# Sheet2.net
KiCad netlist of a schematic drawn in Altium Designer
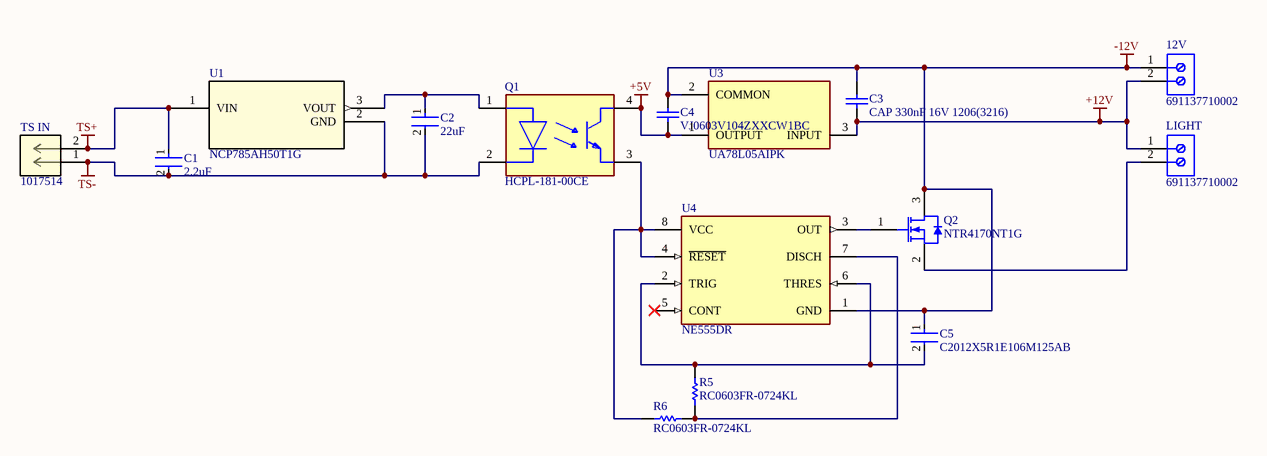
[diagram p0: Sheet2.SchDoc]

(export (version "E")
  (design (tool "Eeschema 10.0.6"))
  (components
    (comp (ref "12V")
      (value "691137710002")
      (footprint "691137710002")
      (libsource (lib "Altium Content Vault") (part "TBL - 1R - 02P - Screw"))
    )
    (comp (ref "C1")
      (value "2.2uF")
      (footprint "FP-C5750-250-0_4-IPC_C")
      (description "Multilayer Ceramic Capacitors 2.2uF ±20% 450V X6S SMD 2220")
      (fields (field (name "TOLERANCE") "20%"))
      (libsource (lib "Altium Content Vault") (part "b4654b650e69147ec39a6b967a45e02"))
    )
    (comp (ref "C2")
      (value "22uF")
      (footprint "FP-GRM21B-0_15-MFG")
      (description "Chip Multilayer Ceramic Capacitors for General Purpose, 0805, 22uF, X5R, 15%, 20%, 6.3V")
      (fields (field (name "VOLTAGE") "6.3V") (field (name "TOLERANCE") "20%"))
      (libsource (lib "Altium Content Vault") (part "b4654b650e69147ec39a6b967a45e02"))
    )
    (comp (ref "C3")
      (value "CAP 330nF 16V 1206(3216)")
      (footprint "CAPC1206(3216)110_M")
      (description "CAP 330nF 16V ±10% 1206 (3216 Metric) Thickness 1.05mm SMD")
      (fields (field (name "TOLERANCE") "Â±10%"))
      (libsource (lib "Altium Content Vault") (part "CAP"))
    )
    (comp (ref "C4")
      (value "VJ0603V104ZXXCW1BC")
      (footprint "CAPC1608X95X40ML15T15")
      (fields (field (name "MANUFACTURER") "Vitramon"))
      (libsource (lib "Altium Content Vault") (part "CAP"))
    )
    (comp (ref "C5")
      (value "C2012X5R1E106M125AB")
      (footprint "FP-C2012-125-0_2-MFG")
      (description "Multilayer Ceramic Capacitors 10μF ±20% 25V X5R SMD 0805")
      (fields (field (name "TOLERANCE") "20%"))
      (libsource (lib "Altium Content Vault") (part "b4654b650e69147ec39a6b967a45e02"))
    )
    (comp (ref "LIGHT")
      (value "691137710002")
      (footprint "691137710002")
      (libsource (lib "Altium Content Vault") (part "TBL - 1R - 02P - Screw"))
    )
    (comp (ref "Q1")
      (value "HCPL-181-00CE")
      (footprint "FP-SO-4-MFG")
      (description "OPTOISO 3.75KV TRANS 4MINIFLAT")
      (fields
        (field (name "OCTOPART") "https://octopart.com/hcpl-181-00ce-broadcom-71128032")
        (field (name "MANUFACTURER") "Broadcom")
      )
      (libsource (lib "Altium Content Vault") (part "474a932ecb3e108566a9d84ede16557"))
    )
    (comp (ref "Q2")
      (value "NTR4170NT1G")
      (footprint "ONSC-SOT-23-3-318-08_V")
      (description "Power MOSFET, 30 V, 3.1 A, Single N-Channe, 3-Pin SOT-23, Pb-Free, Tape and Reel")
      (fields (field (name "MANUFACTURER") "On Semiconductor"))
      (libsource (lib "Altium Content Vault") (part "ONSC-NMOS-G1S2D3-3"))
    )
    (comp (ref "R5")
      (value "RC0603FR-0724KL")
      (footprint "RESC1608X55X25NL10T15")
      (fields (field (name "MANUFACTURER") "Yageo"))
      (libsource (lib "Altium Content Vault") (part "RES"))
    )
    (comp (ref "R6")
      (value "RC0603FR-0724KL")
      (footprint "RESC1608X55X25NL10T15")
      (fields (field (name "MANUFACTURER") "Yageo"))
      (libsource (lib "Altium Content Vault") (part "RES"))
    )
    (comp (ref "TS IN")
      (value "1017514")
      (footprint "CONN_1017514")
      (description "Barrier Strip Terminal Block")
      (libsource (lib "UWindsor Formula Electric") (part "1017514-Symbol-1"))
    )
    (comp (ref "U1")
      (value "NCP785AH50T1G")
      (footprint "SOT-89-3_2P7X4P7_ONS")
      (description "No Description Available")
      (libsource (lib "NCP785AH50T1G") (part "NCP785AH50T1G"))
    )
    (comp (ref "U3")
      (value "UA78L05AIPK")
      (footprint "FP-PK0003A-MFG")
      (description "IC REG LINEAR 5V 100MA SOT89-3")
      (fields
        (field (name "MANUFACTURER") "Texas Instruments")
        (field (name "OCTOPART") "https://octopart.com/ua78l05aipk-texas+instruments-525592")
      )
      (libsource (lib "Altium Content Vault") (part "58e5423477dba73b0af001d1dc47a63"))
    )
    (comp (ref "U4")
      (value "NE555DR")
      (footprint "FP-D0008A-IPC_A")
      (description "IC OSC SGL TIMER 100KHZ 8-SOIC")
      (libsource (lib "Altium Content Vault") (part "a29bba90211dec1890110b94dad7d53"))
    )
  )
  (nets
    (net (code "1") (name "+5V") (class "Default")
      (node (ref "C4") (pin "1") (pinfunction "1_1") (pintype "passive"))
      (node (ref "Q1") (pin "4") (pinfunction "C_4") (pintype "passive"))
      (node (ref "U3") (pin "1") (pinfunction "OUTPUT_1") (pintype "power_in"))
    )
    (net (code "2") (name "+12V") (class "Default")
      (node (ref "12V") (pin "2") (pinfunction "2_2") (pintype "passive"))
      (node (ref "C3") (pin "1") (pinfunction "1_1") (pintype "passive"))
      (node (ref "LIGHT") (pin "1") (pinfunction "1_1") (pintype "passive"))
      (node (ref "U3") (pin "3") (pinfunction "INPUT_3") (pintype "power_in"))
    )
    (net (code "3") (name "-12V") (class "Default")
      (node (ref "12V") (pin "1") (pinfunction "1_1") (pintype "passive"))
      (node (ref "C3") (pin "2") (pinfunction "2_2") (pintype "passive"))
      (node (ref "C4") (pin "2") (pinfunction "2_2") (pintype "passive"))
      (node (ref "C5") (pin "1") (pinfunction "1_1") (pintype "passive"))
      (node (ref "Q2") (pin "3") (pinfunction "D_3") (pintype "passive"))
      (node (ref "U3") (pin "2") (pinfunction "COMMON_2") (pintype "passive"))
      (node (ref "U4") (pin "1") (pinfunction "GND_1") (pintype "power_in"))
    )
    (net (code "4") (name "Net-(Q1-A)") (class "Default")
      (node (ref "C2") (pin "1") (pinfunction "1_1") (pintype "passive"))
      (node (ref "Q1") (pin "1") (pinfunction "A_1") (pintype "passive"))
      (node (ref "U1") (pin "3") (pinfunction "VOUT_3") (pintype "output"))
    )
    (net (code "5") (name "Net-(Q1-E)") (class "Default")
      (node (ref "Q1") (pin "3") (pinfunction "E_3") (pintype "passive"))
      (node (ref "R6") (pin "1") (pinfunction "1_1") (pintype "passive"))
      (node (ref "U4") (pin "4") (pinfunction "~{RESET}_4") (pintype "input"))
      (node (ref "U4") (pin "8") (pinfunction "VCC_8") (pintype "power_in"))
    )
    (net (code "6") (name "Net-(Q2-G)") (class "Default")
      (node (ref "Q2") (pin "1") (pinfunction "G_1") (pintype "passive"))
      (node (ref "U4") (pin "3") (pinfunction "OUT_3") (pintype "output"))
    )
    (net (code "7") (name "Net-(Q2-S)") (class "Default")
      (node (ref "LIGHT") (pin "2") (pinfunction "2_2") (pintype "passive"))
      (node (ref "Q2") (pin "2") (pinfunction "S_2") (pintype "passive"))
    )
    (net (code "8") (name "Net-(U4-DISCH)") (class "Default")
      (node (ref "R5") (pin "1") (pinfunction "1_1") (pintype "passive"))
      (node (ref "R6") (pin "2") (pinfunction "2_2") (pintype "passive"))
      (node (ref "U4") (pin "7") (pinfunction "DISCH_7") (pintype "open_collector"))
    )
    (net (code "9") (name "Net-(U4-THRES)") (class "Default")
      (node (ref "C5") (pin "2") (pinfunction "2_2") (pintype "passive"))
      (node (ref "R5") (pin "2") (pinfunction "2_2") (pintype "passive"))
      (node (ref "U4") (pin "2") (pinfunction "TRIG_2") (pintype "input"))
      (node (ref "U4") (pin "6") (pinfunction "THRES_6") (pintype "input"))
    )
    (net (code "10") (name "TS+") (class "Default")
      (node (ref "C1") (pin "1") (pinfunction "1_1") (pintype "passive"))
      (node (ref "TS IN") (pin "2") (pinfunction "2_2") (pintype "passive"))
      (node (ref "U1") (pin "1") (pinfunction "VIN_1") (pintype "passive"))
    )
    (net (code "11") (name "TS-") (class "Default")
      (node (ref "C1") (pin "2") (pinfunction "2_2") (pintype "passive"))
      (node (ref "C2") (pin "2") (pinfunction "2_2") (pintype "passive"))
      (node (ref "Q1") (pin "2") (pinfunction "C_2") (pintype "passive"))
      (node (ref "TS IN") (pin "1") (pinfunction "1_1") (pintype "passive"))
      (node (ref "U1") (pin "2") (pinfunction "GND_2") (pintype "power_in"))
    )
    (net (code "12") (name "unconnected-(U4-CONT-Pad5)") (class "Default")
      (node (ref "U4") (pin "5") (pinfunction "CONT_5") (pintype "input+no_connect"))
    )
  )
)
